# encoder.net
KiCad netlist of a schematic drawn in EAGLE
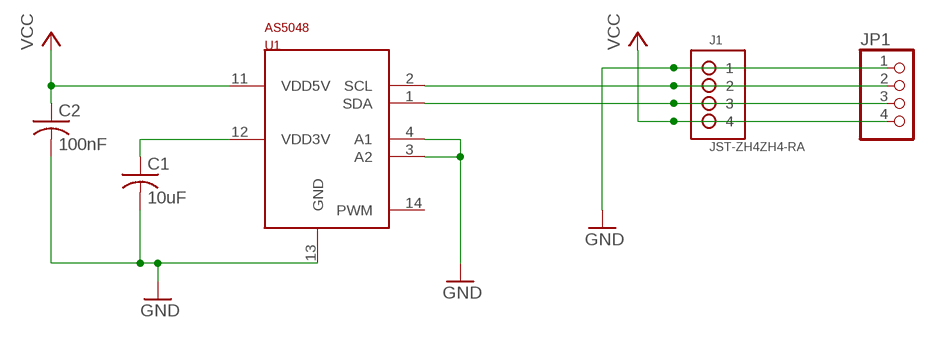
[diagram p0: schematic, sheet 1]

(export (version "E")
  (design (tool "Eeschema 10.0.6"))
  (components
    (comp (ref "C1")
      (value "10uF")
      (footprint "eagle-import:C0603")
      (libsource (lib "eagle-import") (part "C-USC0603"))
    )
    (comp (ref "C2")
      (value "100nF")
      (footprint "eagle-import:C0603")
      (libsource (lib "eagle-import") (part "C-USC0603"))
    )
    (comp (ref "J1")
      (value "JST-ZH4ZH4-RA")
      (footprint "eagle-import:JST_ZH4_RA")
      (libsource (lib "eagle-import") (part "JST-ZH4ZH4-RA"))
    )
    (comp (ref "JP1")
      (value "PINHD-1X4")
      (footprint "eagle-import:1X04")
      (libsource (lib "eagle-import") (part "PINHD-1X4"))
    )
    (comp (ref "U1")
      (value "AS5048BTSSOP14")
      (footprint "eagle-import:TSSOP14")
      (libsource (lib "eagle-import") (part "AS5048BTSSOP14"))
    )
  )
  (nets
    (net (code "1") (name "GND") (class "Default")
      (node (ref "C1") (pin "2") (pinfunction "2_2") (pintype "passive"))
      (node (ref "C2") (pin "2") (pinfunction "2_2") (pintype "passive"))
      (node (ref "J1") (pin "1") (pinfunction "1_1") (pintype "bidirectional"))
      (node (ref "JP1") (pin "1") (pinfunction "1_1") (pintype "passive"))
      (node (ref "U1") (pin "13") (pinfunction "GND_13") (pintype "bidirectional"))
      (node (ref "U1") (pin "3") (pinfunction "A2_3") (pintype "bidirectional"))
      (node (ref "U1") (pin "4") (pinfunction "A1_4") (pintype "bidirectional"))
    )
    (net (code "2") (name "Net-(U1-SCL)") (class "Default")
      (node (ref "J1") (pin "2") (pinfunction "2_2") (pintype "bidirectional"))
      (node (ref "JP1") (pin "2") (pinfunction "2_2") (pintype "passive"))
      (node (ref "U1") (pin "2") (pinfunction "SCL_2") (pintype "bidirectional"))
    )
    (net (code "3") (name "Net-(U1-SDA)") (class "Default")
      (node (ref "J1") (pin "3") (pinfunction "3_3") (pintype "bidirectional"))
      (node (ref "JP1") (pin "3") (pinfunction "3_3") (pintype "passive"))
      (node (ref "U1") (pin "1") (pinfunction "SDA_1") (pintype "bidirectional"))
    )
    (net (code "4") (name "Net-(U1-VDD3V)") (class "Default")
      (node (ref "C1") (pin "1") (pinfunction "1_1") (pintype "passive"))
      (node (ref "U1") (pin "12") (pinfunction "VDD3V_12") (pintype "bidirectional"))
    )
    (net (code "5") (name "VCC") (class "Default")
      (node (ref "C2") (pin "1") (pinfunction "1_1") (pintype "passive"))
      (node (ref "J1") (pin "4") (pinfunction "4_4") (pintype "bidirectional"))
      (node (ref "JP1") (pin "4") (pinfunction "4_4") (pintype "passive"))
      (node (ref "U1") (pin "11") (pinfunction "VDD5V_11") (pintype "bidirectional"))
    )
    (net (code "6") (name "unconnected-(U1-PWM-Pad14)") (class "Default")
      (node (ref "U1") (pin "14") (pinfunction "PWM_14") (pintype "bidirectional"))
    )
  )
)
